# Julia_ABL_Board.net
KiCad netlist of a schematic drawn in EAGLE
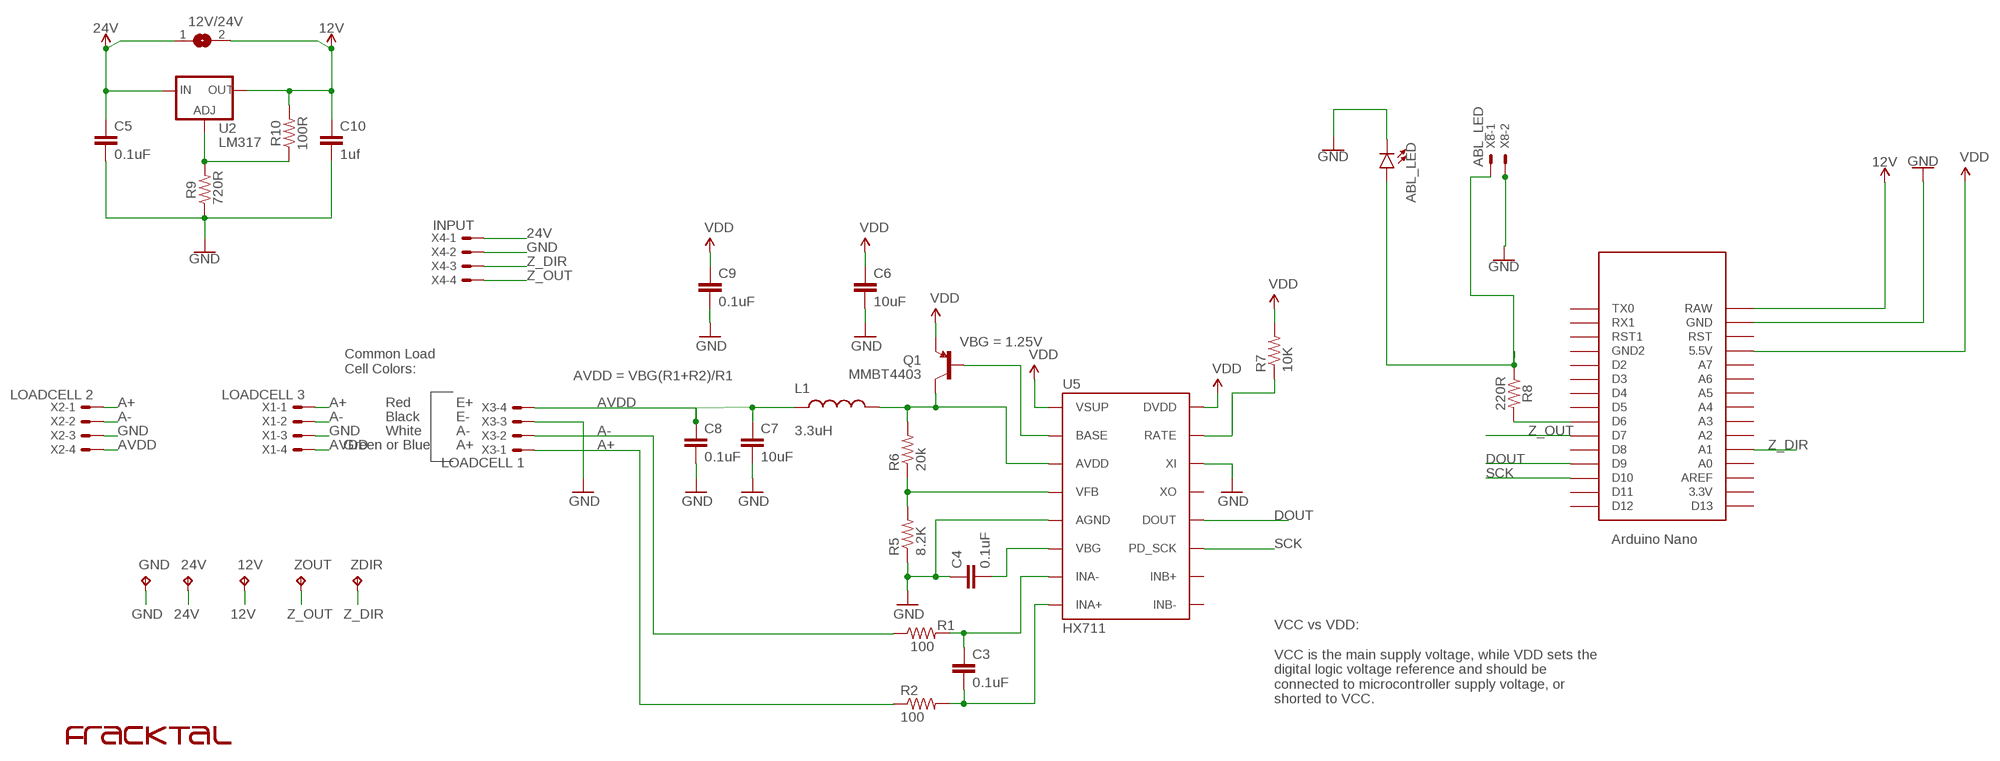
[diagram p0: schematic, sheet 1]

(export (version "E")
  (design (tool "Eeschema 10.0.6"))
  (components
    (comp (ref "12V")
      (value "TPB2,54")
      (footprint "eagle-import:B2,54")
      (libsource (lib "eagle-import") (part "TPB2,54"))
    )
    (comp (ref "12V/24V")
      (value "SJ")
      (footprint "eagle-import:SJ")
      (libsource (lib "eagle-import") (part "SJ"))
    )
    (comp (ref "24V")
      (value "TPB2,54")
      (footprint "eagle-import:B2,54")
      (libsource (lib "eagle-import") (part "TPB2,54"))
    )
    (comp (ref "ABL_LED")
      (value "LED-3MM-NO_SILK")
      (footprint "eagle-import:LED_3MM-NS")
      (libsource (lib "eagle-import") (part "LED-3MM-NO_SILK"))
    )
    (comp (ref "C3")
      (value "0.1uF")
      (footprint "eagle-import:0603-CAP")
      (libsource (lib "eagle-import") (part "0.1UF-25V-5%(0603)"))
    )
    (comp (ref "C4")
      (value "0.1uF")
      (footprint "eagle-import:0603-CAP")
      (libsource (lib "eagle-import") (part "0.1UF-25V-5%(0603)"))
    )
    (comp (ref "C5")
      (value "0.1uF")
      (footprint "eagle-import:0603")
      (libsource (lib "eagle-import") (part "9.0PF-0603-50V-10%"))
    )
    (comp (ref "C6")
      (value "10uF")
      (footprint "eagle-import:1210")
      (libsource (lib "eagle-import") (part "10UF50V20%(1210)"))
    )
    (comp (ref "C7")
      (value "10uF")
      (footprint "eagle-import:1210")
      (libsource (lib "eagle-import") (part "10UF50V20%(1210)"))
    )
    (comp (ref "C8")
      (value "0.1uF")
      (footprint "eagle-import:0603-CAP")
      (libsource (lib "eagle-import") (part "0.1UF-25V-5%(0603)"))
    )
    (comp (ref "C9")
      (value "0.1uF")
      (footprint "eagle-import:0603-CAP")
      (libsource (lib "eagle-import") (part "0.1UF-25V-5%(0603)"))
    )
    (comp (ref "C10")
      (value "1uf")
      (footprint "eagle-import:0603")
      (libsource (lib "eagle-import") (part "9.0PF-0603-50V-10%"))
    )
    (comp (ref "GND")
      (value "TPB2,54")
      (footprint "eagle-import:B2,54")
      (libsource (lib "eagle-import") (part "TPB2,54"))
    )
    (comp (ref "L1")
      (value "3.3uH")
      (footprint "eagle-import:0805")
      (libsource (lib "eagle-import") (part "INDUCTOR0805-IND"))
    )
    (comp (ref "Q1")
      (value "MMBT4403")
      (footprint "eagle-import:SOT23-3")
      (libsource (lib "eagle-import") (part "TRANSISTOR_PNPMMBT4403"))
    )
    (comp (ref "R1")
      (value "100")
      (footprint "eagle-import:0603-RES")
      (libsource (lib "eagle-import") (part "100OHM-1/10W-1%(0603)"))
    )
    (comp (ref "R2")
      (value "100")
      (footprint "eagle-import:0603-RES")
      (libsource (lib "eagle-import") (part "100OHM-1/10W-1%(0603)"))
    )
    (comp (ref "R5")
      (value "8.2K")
      (footprint "eagle-import:0603-RES")
      (libsource (lib "eagle-import") (part "8.2KOHM-1/10W-5%(0603)"))
    )
    (comp (ref "R6")
      (value "20k")
      (footprint "eagle-import:0603-RES")
      (libsource (lib "eagle-import") (part "20KOHM1/10W1%(0603)"))
    )
    (comp (ref "R7")
      (value "10K")
      (footprint "eagle-import:0603-RES")
      (libsource (lib "eagle-import") (part "10KOHM-1/10W-1%(0603)0603"))
    )
    (comp (ref "R8")
      (value "220R")
      (footprint "eagle-import:0603")
      (libsource (lib "eagle-import") (part "RESISTOR0603"))
    )
    (comp (ref "R9")
      (value "720R")
      (footprint "eagle-import:0603")
      (libsource (lib "eagle-import") (part "RESISTOR0603"))
    )
    (comp (ref "R10")
      (value "100R")
      (footprint "eagle-import:0603")
      (libsource (lib "eagle-import") (part "RESISTOR0603"))
    )
    (comp (ref "U$1")
      (value "NANO")
      (footprint "eagle-import:NANO")
      (libsource (lib "eagle-import") (part "NANO"))
    )
    (comp (ref "U$2")
      (value "FRACKTALLOGO")
      (footprint "eagle-import:FRACKTALLOGO")
      (libsource (lib "eagle-import") (part "FRACKTALLOGO"))
    )
    (comp (ref "U2")
      (value "LM317")
      (footprint "eagle-import:SOT223")
      (libsource (lib "eagle-import") (part "V_REG_317SMD"))
    )
    (comp (ref "U5")
      (value "HX711")
      (footprint "eagle-import:SO16")
      (libsource (lib "eagle-import") (part "HX711HX711"))
    )
    (comp (ref "X1")
      (value "LOADCELL 3")
      (footprint "eagle-import:JST-XH-04-PACKAGE-LONG-PAD")
      (libsource (lib "eagle-import") (part "JST-XH-04-PIN-LONG-PAD"))
    )
    (comp (ref "X2")
      (value "LOADCELL 2")
      (footprint "eagle-import:JST-XH-04-PACKAGE-LONG-PAD")
      (libsource (lib "eagle-import") (part "JST-XH-04-PIN-LONG-PAD"))
    )
    (comp (ref "X3")
      (value "LOADCELL 1")
      (footprint "eagle-import:JST-XH-04-PACKAGE-LONG-PAD")
      (libsource (lib "eagle-import") (part "JST-XH-04-PIN-LONG-PAD"))
    )
    (comp (ref "X4")
      (value "INPUT")
      (footprint "eagle-import:JST-XH-04-PACKAGE-LONG-PAD")
      (libsource (lib "eagle-import") (part "JST-XH-04-PIN-LONG-PAD"))
    )
    (comp (ref "X8")
      (value "ABL_LED")
      (footprint "eagle-import:JST-XH-02-PACKAGE-LONG-PAD")
      (libsource (lib "eagle-import") (part "JST-XH-02-PIN-LONG-PAD"))
    )
    (comp (ref "ZDIR")
      (value "TPB2,54")
      (footprint "eagle-import:B2,54")
      (libsource (lib "eagle-import") (part "TPB2,54"))
    )
    (comp (ref "ZOUT")
      (value "TPB2,54")
      (footprint "eagle-import:B2,54")
      (libsource (lib "eagle-import") (part "TPB2,54"))
    )
  )
  (nets
    (net (code "1") (name "/A+") (class "Default")
      (node (ref "R2") (pin "1") (pinfunction "1_1") (pintype "passive"))
      (node (ref "X1") (pin "1") (pinfunction "S_1") (pintype "passive"))
      (node (ref "X2") (pin "1") (pinfunction "S_1") (pintype "passive"))
      (node (ref "X3") (pin "1") (pinfunction "S_1") (pintype "passive"))
    )
    (net (code "2") (name "/A-") (class "Default")
      (node (ref "R1") (pin "1") (pinfunction "1_1") (pintype "passive"))
      (node (ref "X1") (pin "2") (pinfunction "S_2") (pintype "passive"))
      (node (ref "X2") (pin "2") (pinfunction "S_2") (pintype "passive"))
      (node (ref "X3") (pin "2") (pinfunction "S_2") (pintype "passive"))
    )
    (net (code "3") (name "/AVDD") (class "Default")
      (node (ref "C7") (pin "1") (pinfunction "1_1") (pintype "passive"))
      (node (ref "C8") (pin "1") (pinfunction "1_1") (pintype "passive"))
      (node (ref "L1") (pin "1") (pinfunction "1_1") (pintype "passive"))
      (node (ref "X1") (pin "4") (pinfunction "S_4") (pintype "passive"))
      (node (ref "X2") (pin "4") (pinfunction "S_4") (pintype "passive"))
      (node (ref "X3") (pin "4") (pinfunction "S_4") (pintype "passive"))
    )
    (net (code "4") (name "/DOUT") (class "Default")
      (node (ref "U$1") (pin "D9") (pinfunction "D9_D9") (pintype "bidirectional"))
      (node (ref "U5") (pin "12") (pinfunction "DOUT_12") (pintype "bidirectional"))
    )
    (net (code "5") (name "/SCK") (class "Default")
      (node (ref "U$1") (pin "D10") (pinfunction "D10_D10") (pintype "bidirectional"))
      (node (ref "U5") (pin "11") (pinfunction "PD_SCK_11") (pintype "bidirectional"))
    )
    (net (code "6") (name "/Z_DIR") (class "Default")
      (node (ref "U$1") (pin "A1") (pinfunction "A1_A1") (pintype "bidirectional"))
      (node (ref "X4") (pin "3") (pinfunction "S_3") (pintype "passive"))
      (node (ref "ZDIR") (pin "TP") (pinfunction "TP_TP") (pintype "input"))
    )
    (net (code "7") (name "/Z_OUT") (class "Default")
      (node (ref "U$1") (pin "D7") (pinfunction "D7_D7") (pintype "bidirectional"))
      (node (ref "X4") (pin "4") (pinfunction "S_4") (pintype "passive"))
      (node (ref "ZOUT") (pin "TP") (pinfunction "TP_TP") (pintype "input"))
    )
    (net (code "8") (name "12V") (class "Default")
      (node (ref "12V") (pin "TP") (pinfunction "TP_TP") (pintype "input"))
      (node (ref "12V/24V") (pin "2") (pinfunction "2_2") (pintype "passive"))
      (node (ref "C10") (pin "1") (pinfunction "1_1") (pintype "passive"))
      (node (ref "R10") (pin "2") (pinfunction "2_2") (pintype "passive"))
      (node (ref "U$1") (pin "RAW") (pinfunction "RAW_RAW") (pintype "bidirectional"))
      (node (ref "U2") (pin "2") (pinfunction "OUT_2") (pintype "output"))
    )
    (net (code "9") (name "24V") (class "Default")
      (node (ref "12V/24V") (pin "1") (pinfunction "1_1") (pintype "passive"))
      (node (ref "24V") (pin "TP") (pinfunction "TP_TP") (pintype "input"))
      (node (ref "C5") (pin "1") (pinfunction "1_1") (pintype "passive"))
      (node (ref "U2") (pin "3") (pinfunction "IN_3") (pintype "input"))
      (node (ref "X4") (pin "1") (pinfunction "S_1") (pintype "passive"))
    )
    (net (code "10") (name "GND") (class "Default")
      (node (ref "ABL_LED") (pin "K") (pinfunction "C_K") (pintype "passive"))
      (node (ref "C10") (pin "2") (pinfunction "2_2") (pintype "passive"))
      (node (ref "C4") (pin "1") (pinfunction "1_1") (pintype "passive"))
      (node (ref "C5") (pin "2") (pinfunction "2_2") (pintype "passive"))
      (node (ref "C6") (pin "2") (pinfunction "2_2") (pintype "passive"))
      (node (ref "C7") (pin "2") (pinfunction "2_2") (pintype "passive"))
      (node (ref "C8") (pin "2") (pinfunction "2_2") (pintype "passive"))
      (node (ref "C9") (pin "2") (pinfunction "2_2") (pintype "passive"))
      (node (ref "GND") (pin "TP") (pinfunction "TP_TP") (pintype "input"))
      (node (ref "R5") (pin "1") (pinfunction "1_1") (pintype "passive"))
      (node (ref "R9") (pin "1") (pinfunction "1_1") (pintype "passive"))
      (node (ref "U$1") (pin "GND") (pinfunction "GND_GND") (pintype "bidirectional"))
      (node (ref "U5") (pin "14") (pinfunction "XI_14") (pintype "bidirectional"))
      (node (ref "U5") (pin "5") (pinfunction "AGND_5") (pintype "bidirectional"))
      (node (ref "X1") (pin "3") (pinfunction "S_3") (pintype "passive"))
      (node (ref "X2") (pin "3") (pinfunction "S_3") (pintype "passive"))
      (node (ref "X3") (pin "3") (pinfunction "S_3") (pintype "passive"))
      (node (ref "X4") (pin "2") (pinfunction "S_2") (pintype "passive"))
      (node (ref "X8") (pin "2") (pinfunction "S_2") (pintype "passive"))
    )
    (net (code "11") (name "Net-(Q1-B)") (class "Default")
      (node (ref "Q1") (pin "1") (pinfunction "B_1") (pintype "passive"))
      (node (ref "U5") (pin "2") (pinfunction "BASE_2") (pintype "bidirectional"))
    )
    (net (code "12") (name "Net-(Q1-C)") (class "Default")
      (node (ref "L1") (pin "2") (pinfunction "2_2") (pintype "passive"))
      (node (ref "Q1") (pin "3") (pinfunction "C_3") (pintype "passive"))
      (node (ref "R6") (pin "2") (pinfunction "2_2") (pintype "passive"))
      (node (ref "U5") (pin "3") (pinfunction "AVDD_3") (pintype "bidirectional"))
    )
    (net (code "13") (name "Net-(R8-Pad2)") (class "Default")
      (node (ref "R8") (pin "2") (pinfunction "2_2") (pintype "passive"))
      (node (ref "U$1") (pin "D6") (pinfunction "D6_D6") (pintype "bidirectional"))
    )
    (net (code "14") (name "Net-(U2-ADJ)") (class "Default")
      (node (ref "R10") (pin "1") (pinfunction "1_1") (pintype "passive"))
      (node (ref "R9") (pin "2") (pinfunction "2_2") (pintype "passive"))
      (node (ref "U2") (pin "1") (pinfunction "ADJ_1") (pintype "input"))
    )
    (net (code "15") (name "Net-(U5-INA+)") (class "Default")
      (node (ref "C3") (pin "2") (pinfunction "2_2") (pintype "passive"))
      (node (ref "R2") (pin "2") (pinfunction "2_2") (pintype "passive"))
      (node (ref "U5") (pin "8") (pinfunction "INA+_8") (pintype "bidirectional"))
    )
    (net (code "16") (name "Net-(U5-INA-)") (class "Default")
      (node (ref "C3") (pin "1") (pinfunction "1_1") (pintype "passive"))
      (node (ref "R1") (pin "2") (pinfunction "2_2") (pintype "passive"))
      (node (ref "U5") (pin "7") (pinfunction "INA-_7") (pintype "bidirectional"))
    )
    (net (code "17") (name "Net-(U5-RATE)") (class "Default")
      (node (ref "R7") (pin "1") (pinfunction "1_1") (pintype "passive"))
      (node (ref "U5") (pin "15") (pinfunction "RATE_15") (pintype "bidirectional"))
    )
    (net (code "18") (name "Net-(U5-VBG)") (class "Default")
      (node (ref "C4") (pin "2") (pinfunction "2_2") (pintype "passive"))
      (node (ref "U5") (pin "6") (pinfunction "VBG_6") (pintype "bidirectional"))
    )
    (net (code "19") (name "Net-(U5-VFB)") (class "Default")
      (node (ref "R5") (pin "2") (pinfunction "2_2") (pintype "passive"))
      (node (ref "R6") (pin "1") (pinfunction "1_1") (pintype "passive"))
      (node (ref "U5") (pin "4") (pinfunction "VFB_4") (pintype "bidirectional"))
    )
    (net (code "20") (name "Net-(X8A-S)") (class "Default")
      (node (ref "ABL_LED") (pin "A") (pinfunction "A_A") (pintype "passive"))
      (node (ref "R8") (pin "1") (pinfunction "1_1") (pintype "passive"))
      (node (ref "X8") (pin "1") (pinfunction "S_1") (pintype "passive"))
    )
    (net (code "21") (name "VDD") (class "Default")
      (node (ref "C6") (pin "1") (pinfunction "1_1") (pintype "passive"))
      (node (ref "C9") (pin "1") (pinfunction "1_1") (pintype "passive"))
      (node (ref "Q1") (pin "2") (pinfunction "E_2") (pintype "passive"))
      (node (ref "R7") (pin "2") (pinfunction "2_2") (pintype "passive"))
      (node (ref "U$1") (pin "5V") (pinfunction "5.5V_5V") (pintype "bidirectional"))
      (node (ref "U5") (pin "1") (pinfunction "VSUP_1") (pintype "bidirectional"))
      (node (ref "U5") (pin "16") (pinfunction "DVDD_16") (pintype "bidirectional"))
    )
    (net (code "22") (name "unconnected-(U$1-GND2-PadGND1)") (class "Default")
      (node (ref "U$1") (pin "GND1") (pinfunction "GND2_GND1") (pintype "bidirectional"))
    )
    (net (code "23") (name "unconnected-(U$1-Pad3.3V)") (class "Default")
      (node (ref "U$1") (pin "3.3V") (pinfunction "3.3V_3.3V") (pintype "bidirectional"))
    )
    (net (code "24") (name "unconnected-(U$1-PadA0)") (class "Default")
      (node (ref "U$1") (pin "A0") (pinfunction "A0_A0") (pintype "bidirectional"))
    )
    (net (code "25") (name "unconnected-(U$1-PadA2)") (class "Default")
      (node (ref "U$1") (pin "A2") (pinfunction "A2_A2") (pintype "bidirectional"))
    )
    (net (code "26") (name "unconnected-(U$1-PadA3)") (class "Default")
      (node (ref "U$1") (pin "A3") (pinfunction "A3_A3") (pintype "bidirectional"))
    )
    (net (code "27") (name "unconnected-(U$1-PadA4)") (class "Default")
      (node (ref "U$1") (pin "A4") (pinfunction "A4_A4") (pintype "bidirectional"))
    )
    (net (code "28") (name "unconnected-(U$1-PadA5)") (class "Default")
      (node (ref "U$1") (pin "A5") (pinfunction "A5_A5") (pintype "bidirectional"))
    )
    (net (code "29") (name "unconnected-(U$1-PadA6)") (class "Default")
      (node (ref "U$1") (pin "A6") (pinfunction "A6_A6") (pintype "bidirectional"))
    )
    (net (code "30") (name "unconnected-(U$1-PadA7)") (class "Default")
      (node (ref "U$1") (pin "A7") (pinfunction "A7_A7") (pintype "bidirectional"))
    )
    (net (code "31") (name "unconnected-(U$1-PadAREF)") (class "Default")
      (node (ref "U$1") (pin "AREF") (pinfunction "AREF_AREF") (pintype "bidirectional"))
    )
    (net (code "32") (name "unconnected-(U$1-PadD2)") (class "Default")
      (node (ref "U$1") (pin "D2") (pinfunction "D2_D2") (pintype "bidirectional"))
    )
    (net (code "33") (name "unconnected-(U$1-PadD3)") (class "Default")
      (node (ref "U$1") (pin "D3") (pinfunction "D3_D3") (pintype "bidirectional"))
    )
    (net (code "34") (name "unconnected-(U$1-PadD4)") (class "Default")
      (node (ref "U$1") (pin "D4") (pinfunction "D4_D4") (pintype "bidirectional"))
    )
    (net (code "35") (name "unconnected-(U$1-PadD5)") (class "Default")
      (node (ref "U$1") (pin "D5") (pinfunction "D5_D5") (pintype "bidirectional"))
    )
    (net (code "36") (name "unconnected-(U$1-PadD8)") (class "Default")
      (node (ref "U$1") (pin "D8") (pinfunction "D8_D8") (pintype "bidirectional"))
    )
    (net (code "37") (name "unconnected-(U$1-PadD11)") (class "Default")
      (node (ref "U$1") (pin "D11") (pinfunction "D11_D11") (pintype "bidirectional"))
    )
    (net (code "38") (name "unconnected-(U$1-PadD12)") (class "Default")
      (node (ref "U$1") (pin "D12") (pinfunction "D12_D12") (pintype "bidirectional"))
    )
    (net (code "39") (name "unconnected-(U$1-PadD13)") (class "Default")
      (node (ref "U$1") (pin "D13") (pinfunction "D13_D13") (pintype "bidirectional"))
    )
    (net (code "40") (name "unconnected-(U$1-PadICSP1)") (class "Default")
      (node (ref "U$1") (pin "ICSP1") (pinfunction "ICSP1_ICSP1") (pintype "bidirectional"))
    )
    (net (code "41") (name "unconnected-(U$1-PadICSP2)") (class "Default")
      (node (ref "U$1") (pin "ICSP2") (pinfunction "ICSP2_ICSP2") (pintype "bidirectional"))
    )
    (net (code "42") (name "unconnected-(U$1-PadICSP3)") (class "Default")
      (node (ref "U$1") (pin "ICSP3") (pinfunction "ICSP3_ICSP3") (pintype "bidirectional"))
    )
    (net (code "43") (name "unconnected-(U$1-PadICSP4)") (class "Default")
      (node (ref "U$1") (pin "ICSP4") (pinfunction "ICSP4_ICSP4") (pintype "bidirectional"))
    )
    (net (code "44") (name "unconnected-(U$1-PadICSP5)") (class "Default")
      (node (ref "U$1") (pin "ICSP5") (pinfunction "ICSP5_ICSP5") (pintype "bidirectional"))
    )
    (net (code "45") (name "unconnected-(U$1-PadICSP6)") (class "Default")
      (node (ref "U$1") (pin "ICSP6") (pinfunction "ICSP6_ICSP6") (pintype "bidirectional"))
    )
    (net (code "46") (name "unconnected-(U$1-PadRST)") (class "Default")
      (node (ref "U$1") (pin "RST") (pinfunction "RST_RST") (pintype "bidirectional"))
    )
    (net (code "47") (name "unconnected-(U$1-PadRST1)") (class "Default")
      (node (ref "U$1") (pin "RST1") (pinfunction "RST1_RST1") (pintype "bidirectional"))
    )
    (net (code "48") (name "unconnected-(U$1-PadRX1)") (class "Default")
      (node (ref "U$1") (pin "RX1") (pinfunction "RX1_RX1") (pintype "bidirectional"))
    )
    (net (code "49") (name "unconnected-(U$1-PadTX0)") (class "Default")
      (node (ref "U$1") (pin "TX0") (pinfunction "TX0_TX0") (pintype "bidirectional"))
    )
    (net (code "50") (name "unconnected-(U5-INB+-Pad10)") (class "Default")
      (node (ref "U5") (pin "10") (pinfunction "INB+_10") (pintype "bidirectional"))
    )
    (net (code "51") (name "unconnected-(U5-INB--Pad9)") (class "Default")
      (node (ref "U5") (pin "9") (pinfunction "INB-_9") (pintype "bidirectional"))
    )
    (net (code "52") (name "unconnected-(U5-XO-Pad13)") (class "Default")
      (node (ref "U5") (pin "13") (pinfunction "XO_13") (pintype "bidirectional"))
    )
  )
)
